# sata-hub.net
KiCad netlist of a schematic drawn in EAGLE
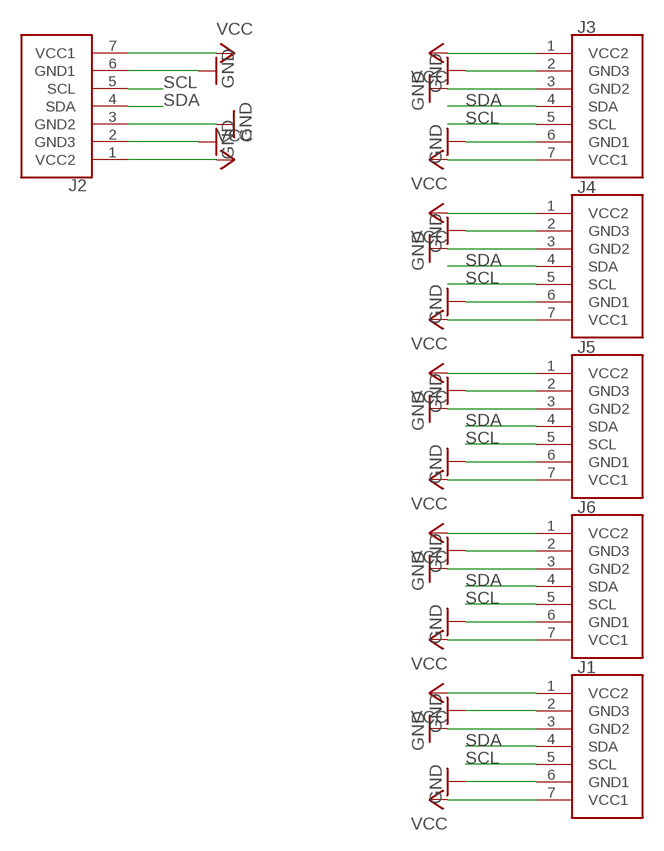
[diagram p0: schematic, sheet 1]

(export (version "E")
  (design (tool "Eeschema 10.0.6"))
  (components
    (comp (ref "J1")
      (value "SATA7-RA")
      (footprint "eagle-import:SATA7-RA")
      (libsource (lib "eagle-import") (part "SATA7-RA"))
    )
    (comp (ref "J2")
      (value "SATA7-RA")
      (footprint "eagle-import:SATA7-RA")
      (libsource (lib "eagle-import") (part "SATA7-RA"))
    )
    (comp (ref "J3")
      (value "SATA7-RA")
      (footprint "eagle-import:SATA7-RA")
      (libsource (lib "eagle-import") (part "SATA7-RA"))
    )
    (comp (ref "J4")
      (value "SATA7-RA")
      (footprint "eagle-import:SATA7-RA")
      (libsource (lib "eagle-import") (part "SATA7-RA"))
    )
    (comp (ref "J5")
      (value "SATA7-RA")
      (footprint "eagle-import:SATA7-RA")
      (libsource (lib "eagle-import") (part "SATA7-RA"))
    )
    (comp (ref "J6")
      (value "SATA7-RA")
      (footprint "eagle-import:SATA7-RA")
      (libsource (lib "eagle-import") (part "SATA7-RA"))
    )
  )
  (nets
    (net (code "1") (name "/SCL") (class "Default")
      (node (ref "J1") (pin "5") (pinfunction "SCL_5") (pintype "bidirectional"))
      (node (ref "J2") (pin "5") (pinfunction "SCL_5") (pintype "bidirectional"))
      (node (ref "J3") (pin "5") (pinfunction "SCL_5") (pintype "bidirectional"))
      (node (ref "J4") (pin "5") (pinfunction "SCL_5") (pintype "bidirectional"))
      (node (ref "J5") (pin "5") (pinfunction "SCL_5") (pintype "bidirectional"))
      (node (ref "J6") (pin "5") (pinfunction "SCL_5") (pintype "bidirectional"))
    )
    (net (code "2") (name "/SDA") (class "Default")
      (node (ref "J1") (pin "4") (pinfunction "SDA_4") (pintype "bidirectional"))
      (node (ref "J2") (pin "4") (pinfunction "SDA_4") (pintype "bidirectional"))
      (node (ref "J3") (pin "4") (pinfunction "SDA_4") (pintype "bidirectional"))
      (node (ref "J4") (pin "4") (pinfunction "SDA_4") (pintype "bidirectional"))
      (node (ref "J5") (pin "4") (pinfunction "SDA_4") (pintype "bidirectional"))
      (node (ref "J6") (pin "4") (pinfunction "SDA_4") (pintype "bidirectional"))
    )
    (net (code "3") (name "GND") (class "Default")
      (node (ref "J1") (pin "2") (pinfunction "GND3_2") (pintype "power_in"))
      (node (ref "J1") (pin "3") (pinfunction "GND2_3") (pintype "power_in"))
      (node (ref "J1") (pin "6") (pinfunction "GND1_6") (pintype "power_in"))
      (node (ref "J2") (pin "2") (pinfunction "GND3_2") (pintype "power_in"))
      (node (ref "J2") (pin "3") (pinfunction "GND2_3") (pintype "power_in"))
      (node (ref "J2") (pin "6") (pinfunction "GND1_6") (pintype "power_in"))
      (node (ref "J3") (pin "2") (pinfunction "GND3_2") (pintype "power_in"))
      (node (ref "J3") (pin "3") (pinfunction "GND2_3") (pintype "power_in"))
      (node (ref "J3") (pin "6") (pinfunction "GND1_6") (pintype "power_in"))
      (node (ref "J4") (pin "2") (pinfunction "GND3_2") (pintype "power_in"))
      (node (ref "J4") (pin "3") (pinfunction "GND2_3") (pintype "power_in"))
      (node (ref "J4") (pin "6") (pinfunction "GND1_6") (pintype "power_in"))
      (node (ref "J5") (pin "2") (pinfunction "GND3_2") (pintype "power_in"))
      (node (ref "J5") (pin "3") (pinfunction "GND2_3") (pintype "power_in"))
      (node (ref "J5") (pin "6") (pinfunction "GND1_6") (pintype "power_in"))
      (node (ref "J6") (pin "2") (pinfunction "GND3_2") (pintype "power_in"))
      (node (ref "J6") (pin "3") (pinfunction "GND2_3") (pintype "power_in"))
      (node (ref "J6") (pin "6") (pinfunction "GND1_6") (pintype "power_in"))
    )
    (net (code "4") (name "VCC") (class "Default")
      (node (ref "J1") (pin "1") (pinfunction "VCC2_1") (pintype "power_in"))
      (node (ref "J1") (pin "7") (pinfunction "VCC1_7") (pintype "power_in"))
      (node (ref "J2") (pin "1") (pinfunction "VCC2_1") (pintype "power_in"))
      (node (ref "J2") (pin "7") (pinfunction "VCC1_7") (pintype "power_in"))
      (node (ref "J3") (pin "1") (pinfunction "VCC2_1") (pintype "power_in"))
      (node (ref "J3") (pin "7") (pinfunction "VCC1_7") (pintype "power_in"))
      (node (ref "J4") (pin "1") (pinfunction "VCC2_1") (pintype "power_in"))
      (node (ref "J4") (pin "7") (pinfunction "VCC1_7") (pintype "power_in"))
      (node (ref "J5") (pin "1") (pinfunction "VCC2_1") (pintype "power_in"))
      (node (ref "J5") (pin "7") (pinfunction "VCC1_7") (pintype "power_in"))
      (node (ref "J6") (pin "1") (pinfunction "VCC2_1") (pintype "power_in"))
      (node (ref "J6") (pin "7") (pinfunction "VCC1_7") (pintype "power_in"))
    )
  )
)
